# Power_distribution.net
KiCad netlist of a schematic drawn in EAGLE
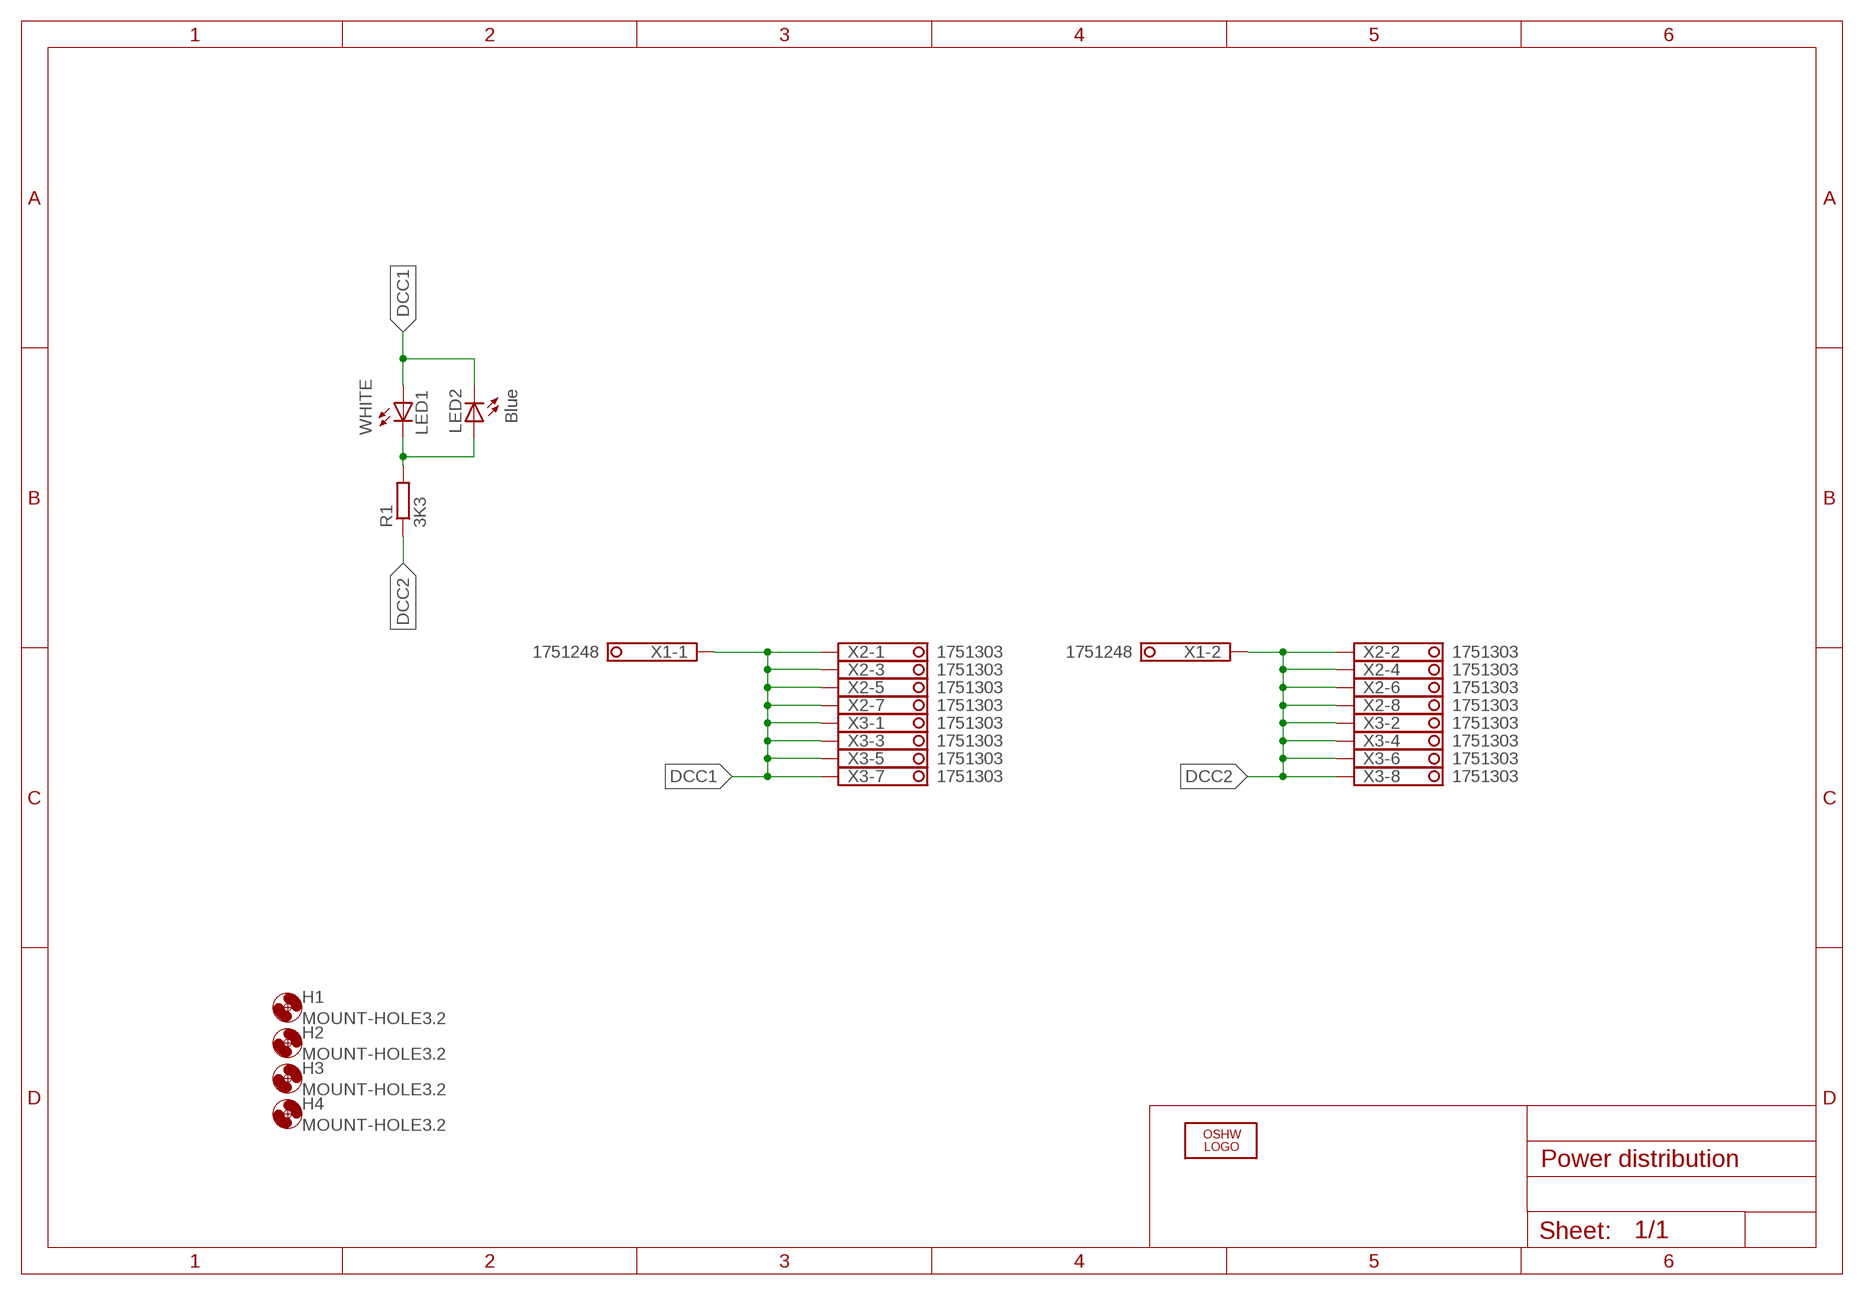
[diagram p0: schematic, sheet 1]

(export (version "E")
  (design (tool "Eeschema 10.0.6"))
  (components
    (comp (ref "H1")
      (value "MOUNT-HOLE3.2")
      (footprint "eagle-import:3,2")
      (libsource (lib "eagle-import") (part "MOUNT-HOLE3.2"))
    )
    (comp (ref "H2")
      (value "MOUNT-HOLE3.2")
      (footprint "eagle-import:3,2")
      (libsource (lib "eagle-import") (part "MOUNT-HOLE3.2"))
    )
    (comp (ref "H3")
      (value "MOUNT-HOLE3.2")
      (footprint "eagle-import:3,2")
      (libsource (lib "eagle-import") (part "MOUNT-HOLE3.2"))
    )
    (comp (ref "H4")
      (value "MOUNT-HOLE3.2")
      (footprint "eagle-import:3,2")
      (libsource (lib "eagle-import") (part "MOUNT-HOLE3.2"))
    )
    (comp (ref "LED1")
      (value "WHITE")
      (footprint "eagle-import:LED3MM")
      (libsource (lib "eagle-import") (part "LED3MM"))
    )
    (comp (ref "LED2")
      (value "Blue")
      (footprint "eagle-import:LED3MM")
      (libsource (lib "eagle-import") (part "LED3MM"))
    )
    (comp (ref "LOGO1")
      (value "OSHW_LOGO_6MILX0200-NT")
      (footprint "eagle-import:OSHW_6X200_NOTEXT")
      (libsource (lib "eagle-import") (part "OSHW_LOGO_6MILX0200-NT"))
    )
    (comp (ref "R1")
      (value "3K3")
      (footprint "eagle-import:R0805")
      (libsource (lib "eagle-import") (part "R-EU_R0805"))
    )
    (comp (ref "X1")
      (value "1751248")
      (footprint "eagle-import:1751248")
      (libsource (lib "eagle-import") (part "1751248"))
    )
    (comp (ref "X2")
      (value "1751303")
      (footprint "eagle-import:1751303")
      (libsource (lib "eagle-import") (part "1751303"))
    )
    (comp (ref "X3")
      (value "1751303")
      (footprint "eagle-import:1751303")
      (libsource (lib "eagle-import") (part "1751303"))
    )
  )
  (nets
    (net (code "1") (name "DCC1") (class "Default")
      (node (ref "LED1") (pin "A") (pinfunction "A_A") (pintype "passive"))
      (node (ref "LED2") (pin "K") (pinfunction "C_K") (pintype "passive"))
      (node (ref "X1") (pin "1") (pinfunction "K_1") (pintype "passive"))
      (node (ref "X2") (pin "1") (pinfunction "K_1") (pintype "passive"))
      (node (ref "X2") (pin "3") (pinfunction "K_3") (pintype "passive"))
      (node (ref "X2") (pin "5") (pinfunction "K_5") (pintype "passive"))
      (node (ref "X2") (pin "7") (pinfunction "K_7") (pintype "passive"))
      (node (ref "X3") (pin "1") (pinfunction "K_1") (pintype "passive"))
      (node (ref "X3") (pin "3") (pinfunction "K_3") (pintype "passive"))
      (node (ref "X3") (pin "5") (pinfunction "K_5") (pintype "passive"))
      (node (ref "X3") (pin "7") (pinfunction "K_7") (pintype "passive"))
    )
    (net (code "2") (name "DCC2") (class "Default")
      (node (ref "R1") (pin "1") (pinfunction "1_1") (pintype "passive"))
      (node (ref "X1") (pin "2") (pinfunction "K_2") (pintype "passive"))
      (node (ref "X2") (pin "2") (pinfunction "K_2") (pintype "passive"))
      (node (ref "X2") (pin "4") (pinfunction "K_4") (pintype "passive"))
      (node (ref "X2") (pin "6") (pinfunction "K_6") (pintype "passive"))
      (node (ref "X2") (pin "8") (pinfunction "K_8") (pintype "passive"))
      (node (ref "X3") (pin "2") (pinfunction "K_2") (pintype "passive"))
      (node (ref "X3") (pin "4") (pinfunction "K_4") (pintype "passive"))
      (node (ref "X3") (pin "6") (pinfunction "K_6") (pintype "passive"))
      (node (ref "X3") (pin "8") (pinfunction "K_8") (pintype "passive"))
    )
    (net (code "3") (name "Net-(LED1-C)") (class "Default")
      (node (ref "LED1") (pin "K") (pinfunction "C_K") (pintype "passive"))
      (node (ref "LED2") (pin "A") (pinfunction "A_A") (pintype "passive"))
      (node (ref "R1") (pin "2") (pinfunction "2_2") (pintype "passive"))
    )
  )
)
